# Switch1.net
KiCad netlist of a schematic drawn in Altium Designer
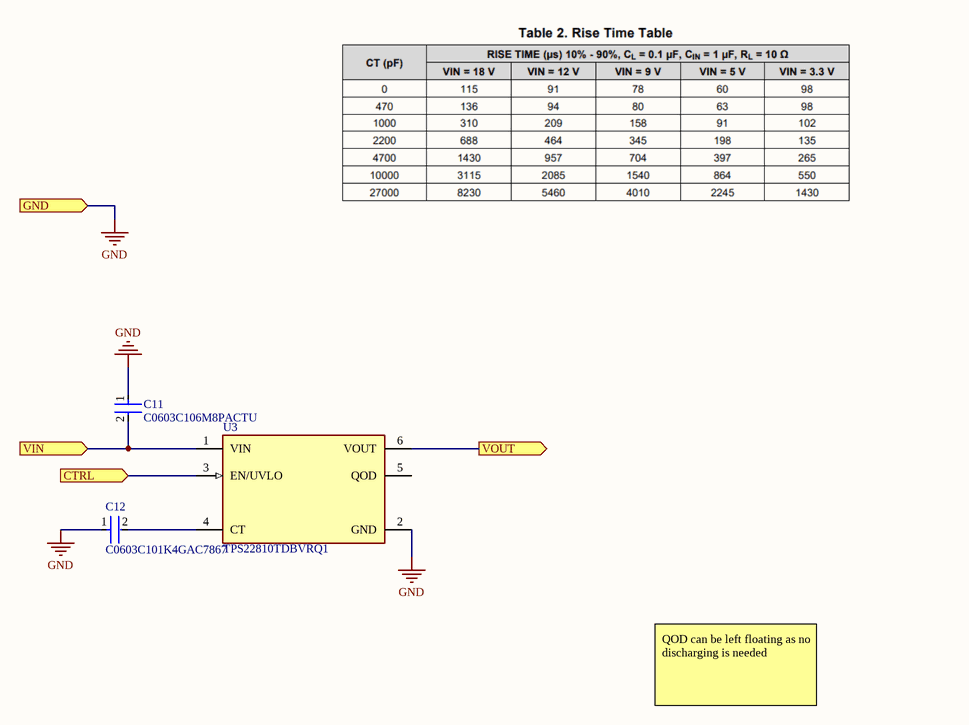
[diagram p0: Switch1.SchDoc]

(export (version "E")
  (design (tool "Eeschema 10.0.6"))
  (components
    (comp (ref "C11")
      (value "C0603C106M8PACTU")
      (footprint "FP-C0603C106M8PACTU-MFG")
      (description "CAP CER 10UF 10V X5R 0603")
      (libsource (lib "Altium Content Vault") (part "02cd4be3c70576c341d710602a673aa"))
    )
    (comp (ref "C12")
      (value "C0603C101K4GAC7867")
      (footprint "FP-C0603C-CF-MFG")
      (description "CAP CER 100PF 16V NP0 0603")
      (fields (field (name "MANUFACTURER") "KEMET") (field (name "TOLERANCE") "0.1"))
      (libsource (lib "Altium Content Vault") (part "b4654b650e69147ec39a6b967a45e02"))
    )
    (comp (ref "U3")
      (value "TPS22810TDBVRQ1")
      (footprint "FP-DBV0006A-MFG")
      (description "IC PWR SWITCH N-CHAN 1:1 SOT23-6")
      (libsource (lib "Altium Content Vault") (part "2d4a2501f31e6718a49a06b44f8b6c7"))
    )
  )
  (nets
    (net (code "1") (name "/CTRL") (class "Default")
      (node (ref "U3") (pin "3") (pinfunction "EN/UVLO_3") (pintype "input"))
    )
    (net (code "2") (name "/VIN") (class "Default")
      (node (ref "C11") (pin "2") (pinfunction "2_2") (pintype "passive"))
      (node (ref "U3") (pin "1") (pinfunction "VIN_1") (pintype "power_in"))
    )
    (net (code "3") (name "/VOUT") (class "Default")
      (node (ref "U3") (pin "6") (pinfunction "VOUT_6") (pintype "passive"))
    )
    (net (code "4") (name "GND") (class "Default")
      (node (ref "C11") (pin "1") (pinfunction "1_1") (pintype "passive"))
      (node (ref "C12") (pin "1") (pinfunction "1_1") (pintype "passive"))
      (node (ref "U3") (pin "2") (pinfunction "GND_2") (pintype "power_in"))
    )
    (net (code "5") (name "Net-(U3-CT)") (class "Default")
      (node (ref "C12") (pin "2") (pinfunction "2_2") (pintype "passive"))
      (node (ref "U3") (pin "4") (pinfunction "CT_4") (pintype "passive"))
    )
    (net (code "6") (name "unconnected-(U3-QOD-Pad5)") (class "Default")
      (node (ref "U3") (pin "5") (pinfunction "QOD_5") (pintype "passive"))
    )
  )
)
